# 5V-Module.net
KiCad netlist of a schematic drawn in EAGLE
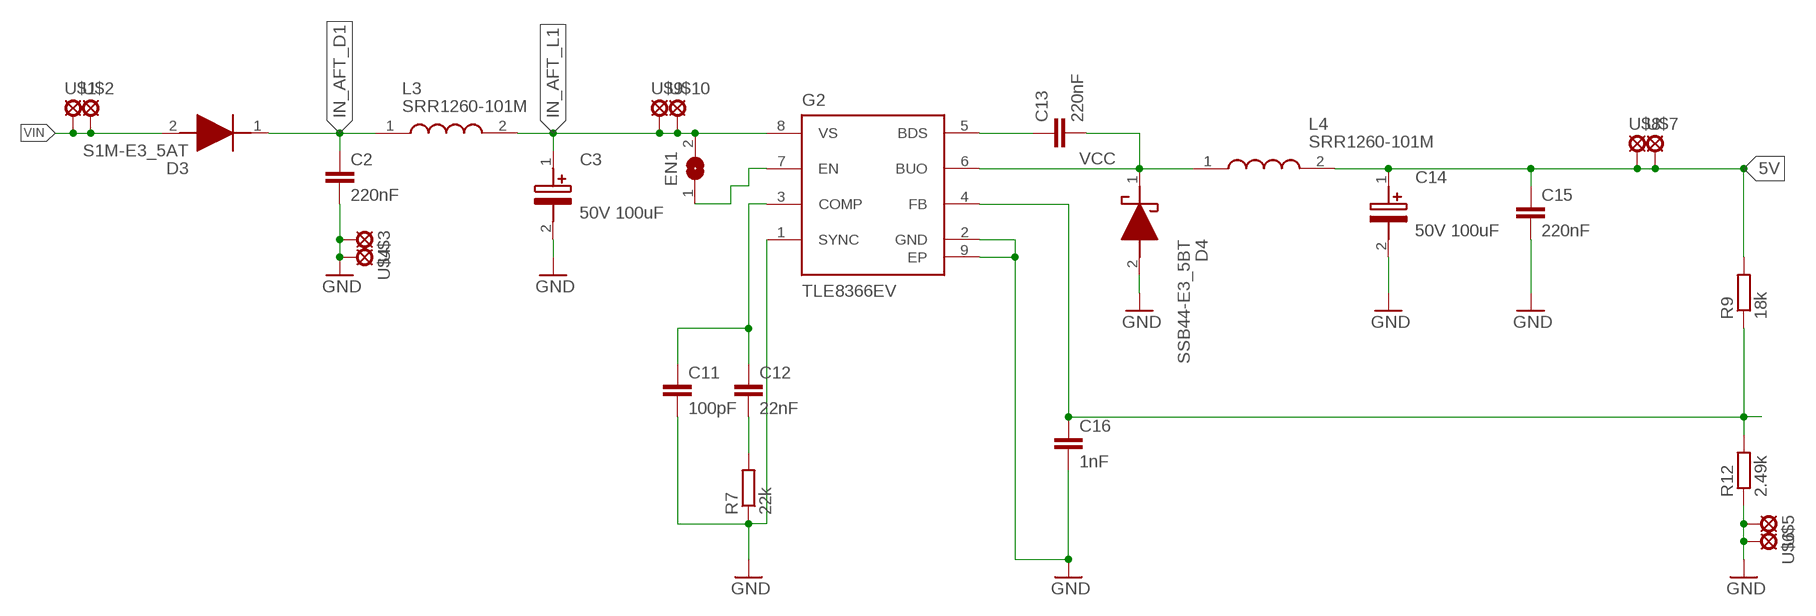
[diagram p0: schematic, sheet 1]

(export (version "E")
  (design (tool "Eeschema 10.0.6"))
  (components
    (comp (ref "C2")
      (value "220nF")
      (footprint "eagle-import:C0603")
      (libsource (lib "eagle-import") (part "C-EUC0603"))
    )
    (comp (ref "C3")
      (value "50V 100uF")
      (footprint "eagle-import:CAPAE830X1050N")
      (fields
        (field (name "MANUFACTURER_PART_NUMBER") "865060653010")
        (field (name "MOUSER_PART_NUMBER") "710-865060653010")
      )
      (libsource (lib "eagle-import") (part "865060653010"))
    )
    (comp (ref "C11")
      (value "100pF")
      (footprint "eagle-import:C0603")
      (libsource (lib "eagle-import") (part "C-EUC0603"))
    )
    (comp (ref "C12")
      (value "22nF")
      (footprint "eagle-import:C0603")
      (libsource (lib "eagle-import") (part "C-EUC0603"))
    )
    (comp (ref "C13")
      (value "220nF")
      (footprint "eagle-import:C0603")
      (libsource (lib "eagle-import") (part "C-EUC0603"))
    )
    (comp (ref "C14")
      (value "50V 100uF")
      (footprint "eagle-import:CAPAE830X1050N")
      (fields
        (field (name "MANUFACTURER_PART_NUMBER") "865060653010")
        (field (name "MOUSER_PART_NUMBER") "710-865060653010")
      )
      (libsource (lib "eagle-import") (part "865060653010"))
    )
    (comp (ref "C15")
      (value "220nF")
      (footprint "eagle-import:C0603")
      (libsource (lib "eagle-import") (part "C-EUC0603"))
    )
    (comp (ref "C16")
      (value "1nF")
      (footprint "eagle-import:C0603")
      (libsource (lib "eagle-import") (part "C-EUC0603"))
    )
    (comp (ref "D3")
      (value "S1M-E3_5AT")
      (footprint "eagle-import:DIOM5127X229N")
      (fields
        (field (name "MANUFACTURER_PART_NUMBER") "S1M-E3/5AT")
        (field (name "MOUSER_PART_NUMBER") "625-S1M-E3/5AT")
      )
      (libsource (lib "eagle-import") (part "S1M-E3_5AT"))
    )
    (comp (ref "D4")
      (value "SSB44-E3_5BT")
      (footprint "eagle-import:DIOM5436X244N")
      (fields
        (field (name "MANUFACTURER_PART_NUMBER") "SSB44-E3/5BT")
        (field (name "MOUSER_PART_NUMBER") "625-SSB44-E3/5BT")
      )
      (libsource (lib "eagle-import") (part "SSB44-E3_5BT"))
    )
    (comp (ref "EN1") (value "SJ") (footprint "eagle-import:SJ") (libsource (lib "eagle-import") (part "SJ")))
    (comp (ref "G2")
      (value "TLE8366EV")
      (footprint "eagle-import:SOIC127P600X170-9N-1")
      (libsource (lib "eagle-import") (part "TLE8366EV"))
    )
    (comp (ref "L3")
      (value "SRR1260-101M")
      (footprint "eagle-import:SRR1260101M")
      (fields (field (name "MOUSER_PART_NUMBER") "652-SRR1260-101M"))
      (libsource (lib "eagle-import") (part "SRR1260-101M"))
    )
    (comp (ref "L4")
      (value "SRR1260-101M")
      (footprint "eagle-import:SRR1260101M")
      (fields (field (name "MOUSER_PART_NUMBER") "652-SRR1260-101M"))
      (libsource (lib "eagle-import") (part "SRR1260-101M"))
    )
    (comp (ref "R7")
      (value "22k")
      (footprint "eagle-import:R0603")
      (libsource (lib "eagle-import") (part "R-EU_R0603"))
    )
    (comp (ref "R9")
      (value "18k")
      (footprint "eagle-import:R0603")
      (libsource (lib "eagle-import") (part "R-EU_R0603"))
    )
    (comp (ref "R12")
      (value "2.49k")
      (footprint "eagle-import:R0603")
      (libsource (lib "eagle-import") (part "R-EU_R0603"))
    )
    (comp (ref "U$1")
      (value "2MM_PAD")
      (footprint "eagle-import:2MM_PAD")
      (libsource (lib "eagle-import") (part "2MM_PAD"))
    )
    (comp (ref "U$2")
      (value "2MM_PAD")
      (footprint "eagle-import:2MM_PAD")
      (libsource (lib "eagle-import") (part "2MM_PAD"))
    )
    (comp (ref "U$3")
      (value "2MM_PAD")
      (footprint "eagle-import:2MM_PAD")
      (libsource (lib "eagle-import") (part "2MM_PAD"))
    )
    (comp (ref "U$4")
      (value "2MM_PAD")
      (footprint "eagle-import:2MM_PAD")
      (libsource (lib "eagle-import") (part "2MM_PAD"))
    )
    (comp (ref "U$5")
      (value "2MM_PAD")
      (footprint "eagle-import:2MM_PAD")
      (libsource (lib "eagle-import") (part "2MM_PAD"))
    )
    (comp (ref "U$6")
      (value "2MM_PAD")
      (footprint "eagle-import:2MM_PAD")
      (libsource (lib "eagle-import") (part "2MM_PAD"))
    )
    (comp (ref "U$7")
      (value "2MM_PAD")
      (footprint "eagle-import:2MM_PAD")
      (libsource (lib "eagle-import") (part "2MM_PAD"))
    )
    (comp (ref "U$8")
      (value "2MM_PAD")
      (footprint "eagle-import:2MM_PAD")
      (libsource (lib "eagle-import") (part "2MM_PAD"))
    )
    (comp (ref "U$9")
      (value "2MM_PAD")
      (footprint "eagle-import:2MM_PAD")
      (libsource (lib "eagle-import") (part "2MM_PAD"))
    )
    (comp (ref "U$10")
      (value "2MM_PAD")
      (footprint "eagle-import:2MM_PAD")
      (libsource (lib "eagle-import") (part "2MM_PAD"))
    )
  )
  (nets
    (net (code "1") (name "/VCC") (class "Default")
      (node (ref "C13") (pin "2") (pinfunction "2_2") (pintype "passive"))
      (node (ref "D4") (pin "1") (pinfunction "K_1") (pintype "bidirectional"))
      (node (ref "G2") (pin "6") (pinfunction "BUO_6") (pintype "output"))
      (node (ref "L4") (pin "1") (pinfunction "1_1") (pintype "bidirectional"))
    )
    (net (code "2") (name "5V") (class "Default")
      (node (ref "C14") (pin "1") (pinfunction "+_1") (pintype "bidirectional"))
      (node (ref "C15") (pin "1") (pinfunction "1_1") (pintype "passive"))
      (node (ref "L4") (pin "2") (pinfunction "2_2") (pintype "bidirectional"))
      (node (ref "R9") (pin "2") (pinfunction "2_2") (pintype "passive"))
      (node (ref "U$7") (pin "P$1") (pinfunction "MP_P$1") (pintype "passive"))
      (node (ref "U$8") (pin "P$1") (pinfunction "MP_P$1") (pintype "passive"))
    )
    (net (code "3") (name "GND") (class "Default")
      (node (ref "C11") (pin "2") (pinfunction "2_2") (pintype "passive"))
      (node (ref "C14") (pin "2") (pinfunction "-_2") (pintype "bidirectional"))
      (node (ref "C15") (pin "2") (pinfunction "2_2") (pintype "passive"))
      (node (ref "C16") (pin "2") (pinfunction "2_2") (pintype "passive"))
      (node (ref "C2") (pin "2") (pinfunction "2_2") (pintype "passive"))
      (node (ref "C3") (pin "2") (pinfunction "-_2") (pintype "bidirectional"))
      (node (ref "D4") (pin "2") (pinfunction "A_2") (pintype "bidirectional"))
      (node (ref "G2") (pin "1") (pinfunction "SYNC_1") (pintype "input"))
      (node (ref "G2") (pin "2") (pinfunction "GND_2") (pintype "power_in"))
      (node (ref "G2") (pin "9") (pinfunction "EP_9") (pintype "power_in"))
      (node (ref "R12") (pin "1") (pinfunction "1_1") (pintype "passive"))
      (node (ref "R7") (pin "1") (pinfunction "1_1") (pintype "passive"))
      (node (ref "U$3") (pin "P$1") (pinfunction "MP_P$1") (pintype "passive"))
      (node (ref "U$4") (pin "P$1") (pinfunction "MP_P$1") (pintype "passive"))
      (node (ref "U$5") (pin "P$1") (pinfunction "MP_P$1") (pintype "passive"))
      (node (ref "U$6") (pin "P$1") (pinfunction "MP_P$1") (pintype "passive"))
    )
    (net (code "4") (name "IN_AFT_D1") (class "Default")
      (node (ref "C2") (pin "1") (pinfunction "1_1") (pintype "passive"))
      (node (ref "D3") (pin "1") (pinfunction "K_1") (pintype "bidirectional"))
      (node (ref "L3") (pin "1") (pinfunction "1_1") (pintype "bidirectional"))
    )
    (net (code "5") (name "IN_AFT_L1") (class "Default")
      (node (ref "C3") (pin "1") (pinfunction "+_1") (pintype "bidirectional"))
      (node (ref "EN1") (pin "2") (pinfunction "2_2") (pintype "passive"))
      (node (ref "G2") (pin "8") (pinfunction "VS_8") (pintype "power_in"))
      (node (ref "L3") (pin "2") (pinfunction "2_2") (pintype "bidirectional"))
      (node (ref "U$10") (pin "P$1") (pinfunction "MP_P$1") (pintype "passive"))
      (node (ref "U$9") (pin "P$1") (pinfunction "MP_P$1") (pintype "passive"))
    )
    (net (code "6") (name "Net-(C12-Pad2)") (class "Default")
      (node (ref "C12") (pin "2") (pinfunction "2_2") (pintype "passive"))
      (node (ref "R7") (pin "2") (pinfunction "2_2") (pintype "passive"))
    )
    (net (code "7") (name "Net-(G2-BDS)") (class "Default")
      (node (ref "C13") (pin "1") (pinfunction "1_1") (pintype "passive"))
      (node (ref "G2") (pin "5") (pinfunction "BDS_5") (pintype "input"))
    )
    (net (code "8") (name "Net-(G2-COMP)") (class "Default")
      (node (ref "C11") (pin "1") (pinfunction "1_1") (pintype "passive"))
      (node (ref "C12") (pin "1") (pinfunction "1_1") (pintype "passive"))
      (node (ref "G2") (pin "3") (pinfunction "COMP_3") (pintype "input"))
    )
    (net (code "9") (name "Net-(G2-EN)") (class "Default")
      (node (ref "EN1") (pin "1") (pinfunction "1_1") (pintype "passive"))
      (node (ref "G2") (pin "7") (pinfunction "EN_7") (pintype "input"))
    )
    (net (code "10") (name "Net-(G2-FB)") (class "Default")
      (node (ref "C16") (pin "1") (pinfunction "1_1") (pintype "passive"))
      (node (ref "G2") (pin "4") (pinfunction "FB_4") (pintype "input"))
      (node (ref "R12") (pin "2") (pinfunction "2_2") (pintype "passive"))
      (node (ref "R9") (pin "1") (pinfunction "1_1") (pintype "passive"))
    )
    (net (code "11") (name "VIN") (class "Default")
      (node (ref "D3") (pin "2") (pinfunction "A_2") (pintype "bidirectional"))
      (node (ref "U$1") (pin "P$1") (pinfunction "MP_P$1") (pintype "passive"))
      (node (ref "U$2") (pin "P$1") (pinfunction "MP_P$1") (pintype "passive"))
    )
  )
)
